# Lights-ctrl_rev03.net
KiCad netlist of a schematic drawn in EAGLE
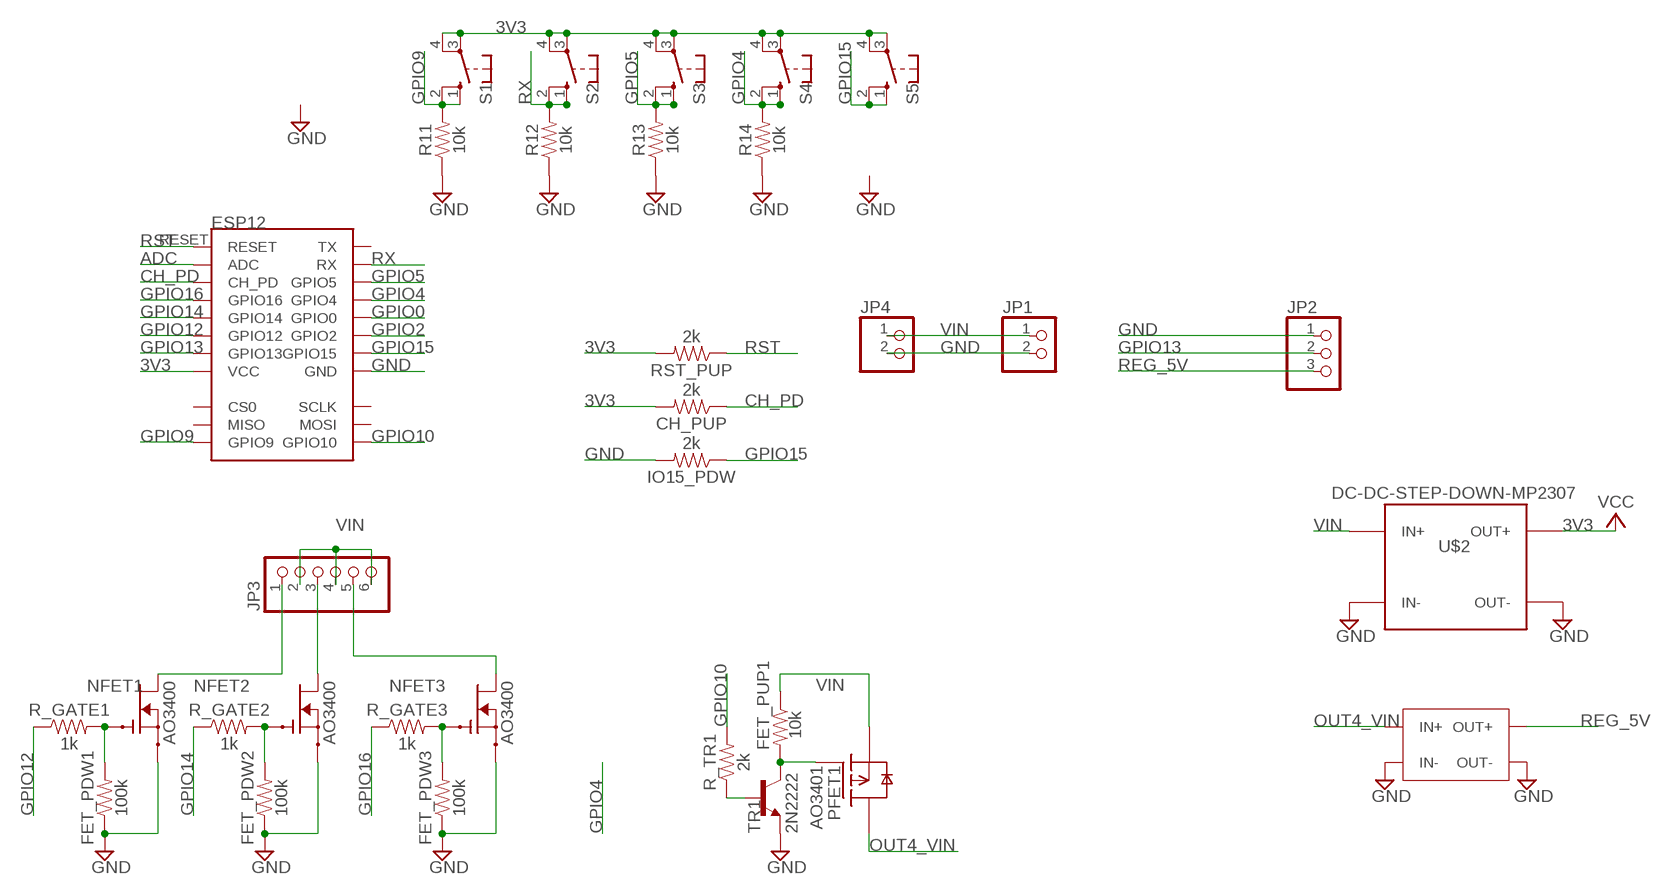
[diagram p0: schematic, sheet 1]

(export (version "E")
  (design (tool "Eeschema 10.0.6"))
  (components
    (comp (ref "CH_PUP")
      (value "2k")
      (footprint "eagle-import:0603")
      (libsource (lib "eagle-import") (part "200KOHM-0603-1/10W-1%"))
    )
    (comp (ref "FET_PDW1")
      (value "100k")
      (footprint "eagle-import:0603")
      (libsource (lib "eagle-import") (part "200KOHM-0603-1/10W-1%"))
    )
    (comp (ref "FET_PDW2")
      (value "100k")
      (footprint "eagle-import:0603")
      (libsource (lib "eagle-import") (part "200KOHM-0603-1/10W-1%"))
    )
    (comp (ref "FET_PDW3")
      (value "100k")
      (footprint "eagle-import:0603")
      (libsource (lib "eagle-import") (part "200KOHM-0603-1/10W-1%"))
    )
    (comp (ref "FET_PUP1")
      (value "10k")
      (footprint "eagle-import:0603")
      (libsource (lib "eagle-import") (part "200KOHM-0603-1/10W-1%"))
    )
    (comp (ref "IO15_PDW")
      (value "2k")
      (footprint "eagle-import:0603")
      (libsource (lib "eagle-import") (part "200KOHM-0603-1/10W-1%"))
    )
    (comp (ref "JP1")
      (value "PINHD-1X2")
      (footprint "eagle-import:1X02")
      (libsource (lib "eagle-import") (part "PINHD-1X2"))
    )
    (comp (ref "JP2")
      (value "PINHD-1X3")
      (footprint "eagle-import:1X03")
      (libsource (lib "eagle-import") (part "PINHD-1X3"))
    )
    (comp (ref "JP3")
      (value "PINHD-1X6/90")
      (footprint "eagle-import:1X06_90")
      (libsource (lib "eagle-import") (part "PINHD-1X6/90"))
    )
    (comp (ref "JP4")
      (value "PINHD-1X2")
      (footprint "eagle-import:1X02")
      (libsource (lib "eagle-import") (part "PINHD-1X2"))
    )
    (comp (ref "NFET1")
      (value "AO3400")
      (footprint "eagle-import:SOT23-3")
      (libsource (lib "eagle-import") (part "AO3400"))
    )
    (comp (ref "NFET2")
      (value "AO3400")
      (footprint "eagle-import:SOT23-3")
      (libsource (lib "eagle-import") (part "AO3400"))
    )
    (comp (ref "NFET3")
      (value "AO3400")
      (footprint "eagle-import:SOT23-3")
      (libsource (lib "eagle-import") (part "AO3400"))
    )
    (comp (ref "PFET1")
      (value "AO3401")
      (footprint "eagle-import:SOT23-3")
      (fields (field (name "MF") "Alpha & Omega Semiconductor"))
      (libsource (lib "eagle-import") (part "AO3401"))
    )
    (comp (ref "R11")
      (value "10k")
      (footprint "eagle-import:0603")
      (libsource (lib "eagle-import") (part "200KOHM-0603-1/10W-1%"))
    )
    (comp (ref "R12")
      (value "10k")
      (footprint "eagle-import:0603")
      (libsource (lib "eagle-import") (part "200KOHM-0603-1/10W-1%"))
    )
    (comp (ref "R13")
      (value "10k")
      (footprint "eagle-import:0603")
      (libsource (lib "eagle-import") (part "200KOHM-0603-1/10W-1%"))
    )
    (comp (ref "R14")
      (value "10k")
      (footprint "eagle-import:0603")
      (libsource (lib "eagle-import") (part "200KOHM-0603-1/10W-1%"))
    )
    (comp (ref "RST_PUP")
      (value "2k")
      (footprint "eagle-import:0603")
      (libsource (lib "eagle-import") (part "200KOHM-0603-1/10W-1%"))
    )
    (comp (ref "R_GATE1")
      (value "1k")
      (footprint "eagle-import:0603")
      (libsource (lib "eagle-import") (part "200KOHM-0603-1/10W-1%"))
    )
    (comp (ref "R_GATE2")
      (value "1k")
      (footprint "eagle-import:0603")
      (libsource (lib "eagle-import") (part "200KOHM-0603-1/10W-1%"))
    )
    (comp (ref "R_GATE3")
      (value "1k")
      (footprint "eagle-import:0603")
      (libsource (lib "eagle-import") (part "200KOHM-0603-1/10W-1%"))
    )
    (comp (ref "R_TR1")
      (value "2k")
      (footprint "eagle-import:0603")
      (libsource (lib "eagle-import") (part "200KOHM-0603-1/10W-1%"))
    )
    (comp (ref "S1")
      (value "10-XX")
      (footprint "eagle-import:B3F-10XX")
      (fields (field (name "MPN") "B3F-1000"))
      (libsource (lib "eagle-import") (part "10-XX"))
    )
    (comp (ref "S2")
      (value "10-XX")
      (footprint "eagle-import:B3F-10XX")
      (fields (field (name "MPN") "B3F-1000"))
      (libsource (lib "eagle-import") (part "10-XX"))
    )
    (comp (ref "S3")
      (value "10-XX")
      (footprint "eagle-import:B3F-10XX")
      (fields (field (name "MPN") "B3F-1000"))
      (libsource (lib "eagle-import") (part "10-XX"))
    )
    (comp (ref "S4")
      (value "10-XX")
      (footprint "eagle-import:B3F-10XX")
      (fields (field (name "MPN") "B3F-1000"))
      (libsource (lib "eagle-import") (part "10-XX"))
    )
    (comp (ref "S5")
      (value "10-XX")
      (footprint "eagle-import:B3F-10XX")
      (fields (field (name "MPN") "B3F-1000"))
      (libsource (lib "eagle-import") (part "10-XX"))
    )
    (comp (ref "TR1")
      (value "2N2222")
      (footprint "eagle-import:SOT23-BEC")
      (libsource (lib "eagle-import") (part "2N2222"))
    )
    (comp (ref "U$1")
      (value "ESP12E-CASTELLATED")
      (footprint "eagle-import:ESP12E-CASTELLATED")
      (libsource (lib "eagle-import") (part "ESP12E-CASTELLATED"))
    )
    (comp (ref "U$2")
      (value "DC-DC-STEP-DOWN-MP2307")
      (footprint "eagle-import:DC-DC-STEP-DOWN-MP2307")
      (libsource (lib "eagle-import") (part "DC-DC-STEP-DOWN-MP2307"))
    )
    (comp (ref "U$4")
      (value "XL4005")
      (footprint "eagle-import:XL4005")
      (libsource (lib "eagle-import") (part "XL4005"))
    )
  )
  (nets
    (net (code "1") (name "/ADC") (class "Default")
      (node (ref "U$1") (pin "ADC") (pinfunction "ADC_ADC") (pintype "bidirectional"))
    )
    (net (code "2") (name "/CH_PD") (class "Default")
      (node (ref "CH_PUP") (pin "1") (pinfunction "1_1") (pintype "passive"))
      (node (ref "U$1") (pin "CH_PD") (pinfunction "CH_PD_CH_PD") (pintype "bidirectional"))
    )
    (net (code "3") (name "/GPIO0") (class "Default")
      (node (ref "U$1") (pin "GPIO0") (pinfunction "GPIO0_GPIO0") (pintype "bidirectional"))
    )
    (net (code "4") (name "/GPIO2") (class "Default")
      (node (ref "U$1") (pin "GPIO2") (pinfunction "GPIO2_GPIO2") (pintype "bidirectional"))
    )
    (net (code "5") (name "/GPIO4") (class "Default")
      (node (ref "R14") (pin "2") (pinfunction "2_2") (pintype "passive"))
      (node (ref "S4") (pin "1") (pinfunction "S_1") (pintype "passive"))
      (node (ref "S4") (pin "2") (pinfunction "S1_2") (pintype "passive"))
      (node (ref "U$1") (pin "GPIO4") (pinfunction "GPIO4_GPIO4") (pintype "bidirectional"))
    )
    (net (code "6") (name "/GPIO5") (class "Default")
      (node (ref "R13") (pin "2") (pinfunction "2_2") (pintype "passive"))
      (node (ref "S3") (pin "1") (pinfunction "S_1") (pintype "passive"))
      (node (ref "S3") (pin "2") (pinfunction "S1_2") (pintype "passive"))
      (node (ref "U$1") (pin "GPIO5") (pinfunction "GPIO5_GPIO5") (pintype "bidirectional"))
    )
    (net (code "7") (name "/GPIO9") (class "Default")
      (node (ref "R11") (pin "2") (pinfunction "2_2") (pintype "passive"))
      (node (ref "S1") (pin "1") (pinfunction "S_1") (pintype "passive"))
      (node (ref "S1") (pin "2") (pinfunction "S1_2") (pintype "passive"))
      (node (ref "U$1") (pin "GPIO9") (pinfunction "GPIO9_GPIO9") (pintype "bidirectional"))
    )
    (net (code "8") (name "/GPIO10") (class "Default")
      (node (ref "R_TR1") (pin "2") (pinfunction "2_2") (pintype "passive"))
      (node (ref "U$1") (pin "GPIO10") (pinfunction "GPIO10_GPIO10") (pintype "bidirectional"))
    )
    (net (code "9") (name "/GPIO12") (class "Default")
      (node (ref "R_GATE1") (pin "1") (pinfunction "1_1") (pintype "passive"))
      (node (ref "U$1") (pin "GPIO12") (pinfunction "GPIO12_GPIO12") (pintype "bidirectional"))
    )
    (net (code "10") (name "/GPIO13") (class "Default")
      (node (ref "JP2") (pin "2") (pinfunction "2_2") (pintype "passive"))
      (node (ref "U$1") (pin "GPIO13") (pinfunction "GPIO13_GPIO13") (pintype "bidirectional"))
    )
    (net (code "11") (name "/GPIO14") (class "Default")
      (node (ref "R_GATE2") (pin "1") (pinfunction "1_1") (pintype "passive"))
      (node (ref "U$1") (pin "GPIO14") (pinfunction "GPIO14_GPIO14") (pintype "bidirectional"))
    )
    (net (code "12") (name "/GPIO15") (class "Default")
      (node (ref "IO15_PDW") (pin "1") (pinfunction "1_1") (pintype "passive"))
      (node (ref "S5") (pin "1") (pinfunction "S_1") (pintype "passive"))
      (node (ref "S5") (pin "2") (pinfunction "S1_2") (pintype "passive"))
      (node (ref "U$1") (pin "GPIO15") (pinfunction "GPIO15_GPIO15") (pintype "bidirectional"))
    )
    (net (code "13") (name "/GPIO16") (class "Default")
      (node (ref "R_GATE3") (pin "1") (pinfunction "1_1") (pintype "passive"))
      (node (ref "U$1") (pin "GPIO16") (pinfunction "GPIO16_GPIO16") (pintype "bidirectional"))
    )
    (net (code "14") (name "/OUT4_VIN") (class "Default")
      (node (ref "PFET1") (pin "3") (pinfunction "D_3") (pintype "passive"))
      (node (ref "U$4") (pin "IN+") (pinfunction "IN+_IN+") (pintype "bidirectional"))
    )
    (net (code "15") (name "/REG_5V") (class "Default")
      (node (ref "JP2") (pin "3") (pinfunction "3_3") (pintype "passive"))
      (node (ref "U$4") (pin "OUT+") (pinfunction "OUT+_OUT+") (pintype "bidirectional"))
    )
    (net (code "16") (name "/RST") (class "Default")
      (node (ref "RST_PUP") (pin "1") (pinfunction "1_1") (pintype "passive"))
      (node (ref "U$1") (pin "RESET") (pinfunction "RESET_RESET") (pintype "bidirectional"))
    )
    (net (code "17") (name "/RX") (class "Default")
      (node (ref "R12") (pin "2") (pinfunction "2_2") (pintype "passive"))
      (node (ref "S2") (pin "1") (pinfunction "S_1") (pintype "passive"))
      (node (ref "S2") (pin "2") (pinfunction "S1_2") (pintype "passive"))
      (node (ref "U$1") (pin "RX") (pinfunction "RX_RX") (pintype "bidirectional"))
    )
    (net (code "18") (name "/VIN") (class "Default")
      (node (ref "FET_PUP1") (pin "1") (pinfunction "1_1") (pintype "passive"))
      (node (ref "JP1") (pin "1") (pinfunction "1_1") (pintype "passive"))
      (node (ref "JP3") (pin "2") (pinfunction "2_2") (pintype "passive"))
      (node (ref "JP3") (pin "4") (pinfunction "4_4") (pintype "passive"))
      (node (ref "JP3") (pin "6") (pinfunction "6_6") (pintype "passive"))
      (node (ref "JP4") (pin "1") (pinfunction "1_1") (pintype "passive"))
      (node (ref "PFET1") (pin "2") (pinfunction "S_2") (pintype "passive"))
      (node (ref "U$2") (pin "IN+") (pinfunction "IN+_IN+") (pintype "bidirectional"))
    )
    (net (code "19") (name "GND") (class "Default")
      (node (ref "FET_PDW1") (pin "1") (pinfunction "1_1") (pintype "passive"))
      (node (ref "FET_PDW2") (pin "1") (pinfunction "1_1") (pintype "passive"))
      (node (ref "FET_PDW3") (pin "1") (pinfunction "1_1") (pintype "passive"))
      (node (ref "IO15_PDW") (pin "2") (pinfunction "2_2") (pintype "passive"))
      (node (ref "JP1") (pin "2") (pinfunction "2_2") (pintype "passive"))
      (node (ref "JP2") (pin "1") (pinfunction "1_1") (pintype "passive"))
      (node (ref "JP4") (pin "2") (pinfunction "2_2") (pintype "passive"))
      (node (ref "NFET1") (pin "2") (pinfunction "S_2") (pintype "passive"))
      (node (ref "NFET2") (pin "2") (pinfunction "S_2") (pintype "passive"))
      (node (ref "NFET3") (pin "2") (pinfunction "S_2") (pintype "passive"))
      (node (ref "R11") (pin "1") (pinfunction "1_1") (pintype "passive"))
      (node (ref "R12") (pin "1") (pinfunction "1_1") (pintype "passive"))
      (node (ref "R13") (pin "1") (pinfunction "1_1") (pintype "passive"))
      (node (ref "R14") (pin "1") (pinfunction "1_1") (pintype "passive"))
      (node (ref "TR1") (pin "E") (pinfunction "E_E") (pintype "passive"))
      (node (ref "U$1") (pin "GND") (pinfunction "GND_GND") (pintype "bidirectional"))
      (node (ref "U$2") (pin "IN-") (pinfunction "IN-_IN-") (pintype "bidirectional"))
      (node (ref "U$2") (pin "OUT-") (pinfunction "OUT-_OUT-") (pintype "bidirectional"))
      (node (ref "U$4") (pin "IN-") (pinfunction "IN-_IN-") (pintype "bidirectional"))
      (node (ref "U$4") (pin "OUT-") (pinfunction "OUT-_OUT-") (pintype "bidirectional"))
    )
    (net (code "20") (name "Net-(NFET1-D)") (class "Default")
      (node (ref "JP3") (pin "1") (pinfunction "1_1") (pintype "passive"))
      (node (ref "NFET1") (pin "3") (pinfunction "D_3") (pintype "passive"))
    )
    (net (code "21") (name "Net-(NFET1-G)") (class "Default")
      (node (ref "FET_PDW1") (pin "2") (pinfunction "2_2") (pintype "passive"))
      (node (ref "NFET1") (pin "1") (pinfunction "G_1") (pintype "passive"))
      (node (ref "R_GATE1") (pin "2") (pinfunction "2_2") (pintype "passive"))
    )
    (net (code "22") (name "Net-(NFET2-D)") (class "Default")
      (node (ref "JP3") (pin "3") (pinfunction "3_3") (pintype "passive"))
      (node (ref "NFET2") (pin "3") (pinfunction "D_3") (pintype "passive"))
    )
    (net (code "23") (name "Net-(NFET2-G)") (class "Default")
      (node (ref "FET_PDW2") (pin "2") (pinfunction "2_2") (pintype "passive"))
      (node (ref "NFET2") (pin "1") (pinfunction "G_1") (pintype "passive"))
      (node (ref "R_GATE2") (pin "2") (pinfunction "2_2") (pintype "passive"))
    )
    (net (code "24") (name "Net-(NFET3-D)") (class "Default")
      (node (ref "JP3") (pin "5") (pinfunction "5_5") (pintype "passive"))
      (node (ref "NFET3") (pin "3") (pinfunction "D_3") (pintype "passive"))
    )
    (net (code "25") (name "Net-(NFET3-G)") (class "Default")
      (node (ref "FET_PDW3") (pin "2") (pinfunction "2_2") (pintype "passive"))
      (node (ref "NFET3") (pin "1") (pinfunction "G_1") (pintype "passive"))
      (node (ref "R_GATE3") (pin "2") (pinfunction "2_2") (pintype "passive"))
    )
    (net (code "26") (name "Net-(PFET1-G)") (class "Default")
      (node (ref "FET_PUP1") (pin "2") (pinfunction "2_2") (pintype "passive"))
      (node (ref "PFET1") (pin "1") (pinfunction "G_1") (pintype "passive"))
      (node (ref "TR1") (pin "C") (pinfunction "C_C") (pintype "passive"))
    )
    (net (code "27") (name "Net-(R_TR1-Pad1)") (class "Default")
      (node (ref "R_TR1") (pin "1") (pinfunction "1_1") (pintype "passive"))
      (node (ref "TR1") (pin "B") (pinfunction "B_B") (pintype "passive"))
    )
    (net (code "28") (name "VCC") (class "Default")
      (node (ref "CH_PUP") (pin "2") (pinfunction "2_2") (pintype "passive"))
      (node (ref "RST_PUP") (pin "2") (pinfunction "2_2") (pintype "passive"))
      (node (ref "S1") (pin "3") (pinfunction "P_3") (pintype "passive"))
      (node (ref "S1") (pin "4") (pinfunction "P1_4") (pintype "passive"))
      (node (ref "S2") (pin "3") (pinfunction "P_3") (pintype "passive"))
      (node (ref "S2") (pin "4") (pinfunction "P1_4") (pintype "passive"))
      (node (ref "S3") (pin "3") (pinfunction "P_3") (pintype "passive"))
      (node (ref "S3") (pin "4") (pinfunction "P1_4") (pintype "passive"))
      (node (ref "S4") (pin "3") (pinfunction "P_3") (pintype "passive"))
      (node (ref "S4") (pin "4") (pinfunction "P1_4") (pintype "passive"))
      (node (ref "S5") (pin "3") (pinfunction "P_3") (pintype "passive"))
      (node (ref "S5") (pin "4") (pinfunction "P1_4") (pintype "passive"))
      (node (ref "U$1") (pin "VCC") (pinfunction "VCC_VCC") (pintype "bidirectional"))
      (node (ref "U$2") (pin "OUT+") (pinfunction "OUT+_OUT+") (pintype "bidirectional"))
    )
    (net (code "29") (name "unconnected-(U$1-PadCS0)") (class "Default")
      (node (ref "U$1") (pin "CS0") (pinfunction "CS0_CS0") (pintype "bidirectional"))
    )
    (net (code "30") (name "unconnected-(U$1-PadMISO)") (class "Default")
      (node (ref "U$1") (pin "MISO") (pinfunction "MISO_MISO") (pintype "bidirectional"))
    )
    (net (code "31") (name "unconnected-(U$1-PadMOSI)") (class "Default")
      (node (ref "U$1") (pin "MOSI") (pinfunction "MOSI_MOSI") (pintype "bidirectional"))
    )
    (net (code "32") (name "unconnected-(U$1-PadSCLK)") (class "Default")
      (node (ref "U$1") (pin "SCLK") (pinfunction "SCLK_SCLK") (pintype "bidirectional"))
    )
    (net (code "33") (name "unconnected-(U$1-PadTX)") (class "Default")
      (node (ref "U$1") (pin "TX") (pinfunction "TX_TX") (pintype "bidirectional"))
    )
  )
)
